# design.net
KiCad netlist of a schematic drawn in Altium Designer
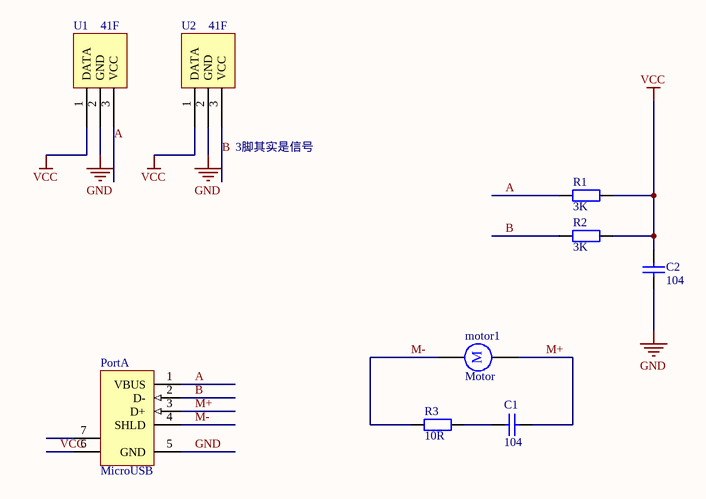
[diagram p0: 电机小板（霍尔编码器）的原理图.SchDoc]

(export (version "E")
  (design (tool "Eeschema 10.0.6"))
  (components
    (comp (ref "C1")
      (value "104")
      (footprint "0805")
      (description "Capacitor")
      (fields (field (name "Comment") "Cap") (field (name "PUBLISHER") "Altium Limited"))
      (libsource (lib "Miscellaneous Devices") (part "Cap"))
    )
    (comp (ref "C2")
      (value "104")
      (footprint "0805")
      (description "Capacitor")
      (fields (field (name "Comment") "Cap") (field (name "PUBLISHER") "Altium Limited"))
      (libsource (lib "Miscellaneous Devices") (part "Cap"))
    )
    (comp (ref "motor1")
      (value "Motor")
      (footprint "RB5-10.5")
      (description "Motor, General Kind")
      (fields (field (name "PUBLISHER") "Altium Limited"))
      (libsource (lib "Miscellaneous Devices") (part "Motor"))
    )
    (comp (ref "PortA")
      (value "MicroUSB")
      (footprint "USB6P")
      (description "USB 2.0, Right Angle, SMT, A Type, Receptacle, 5 Position, Black")
      (fields (field (name "PUBLISHER") "Altium Limited"))
      (libsource (lib "F300") (part "440478-2"))
    )
    (comp (ref "R1")
      (value "3K")
      (footprint "0805")
      (description "Resistor")
      (fields (field (name "Comment") "res2") (field (name "PUBLISHER") "Altium Limited"))
      (libsource (lib "Miscellaneous Devices") (part "Res2"))
    )
    (comp (ref "R2")
      (value "3K")
      (footprint "0805")
      (description "Resistor")
      (fields (field (name "Comment") "res2") (field (name "PUBLISHER") "Altium Limited"))
      (libsource (lib "Miscellaneous Devices") (part "Res2"))
    )
    (comp (ref "R3")
      (value "10R")
      (footprint "0805")
      (description "Resistor")
      (fields (field (name "Comment") "res2") (field (name "PUBLISHER") "Altium Limited"))
      (libsource (lib "Miscellaneous Devices") (part "Res2"))
    )
    (comp (ref "U1") (value "41F") (footprint "HS0038") (libsource (lib "Schlib1") (part "HS0038")))
    (comp (ref "U2") (value "41F") (footprint "HS0038") (libsource (lib "Schlib1") (part "HS0038")))
  )
  (nets
    (net (code "1") (name "/A") (class "Default")
      (node (ref "PortA") (pin "1") (pinfunction "VBUS_1") (pintype "power_in"))
      (node (ref "R1") (pin "1") (pinfunction "1_1") (pintype "passive"))
      (node (ref "U1") (pin "3") (pinfunction "VCC_3") (pintype "passive"))
    )
    (net (code "2") (name "/B") (class "Default")
      (node (ref "PortA") (pin "2") (pinfunction "D-_2") (pintype "input"))
      (node (ref "R2") (pin "1") (pinfunction "1_1") (pintype "passive"))
      (node (ref "U2") (pin "3") (pinfunction "VCC_3") (pintype "passive"))
    )
    (net (code "3") (name "/M+") (class "Default")
      (node (ref "C1") (pin "1") (pinfunction "1_1") (pintype "passive"))
      (node (ref "PortA") (pin "3") (pinfunction "D+_3") (pintype "input"))
      (node (ref "motor1") (pin "2") (pinfunction "2_2") (pintype "passive"))
    )
    (net (code "4") (name "/M-") (class "Default")
      (node (ref "PortA") (pin "4") (pinfunction "SHLD_4") (pintype "passive"))
      (node (ref "R3") (pin "1") (pinfunction "1_1") (pintype "passive"))
      (node (ref "motor1") (pin "1") (pinfunction "1_1") (pintype "passive"))
    )
    (net (code "5") (name "GND") (class "Default")
      (node (ref "C2") (pin "2") (pinfunction "2_2") (pintype "passive"))
      (node (ref "PortA") (pin "5") (pinfunction "GND_5") (pintype "power_in"))
      (node (ref "U1") (pin "2") (pinfunction "GND_2") (pintype "passive"))
      (node (ref "U2") (pin "2") (pinfunction "GND_2") (pintype "passive"))
    )
    (net (code "6") (name "Net-(C1-Pad2)") (class "Default")
      (node (ref "C1") (pin "2") (pinfunction "2_2") (pintype "passive"))
      (node (ref "R3") (pin "2") (pinfunction "2_2") (pintype "passive"))
    )
    (net (code "7") (name "VCC") (class "Default")
      (node (ref "C2") (pin "1") (pinfunction "1_1") (pintype "passive"))
      (node (ref "PortA") (pin "6") (pinfunction "SHLD_6") (pintype "passive"))
      (node (ref "R1") (pin "2") (pinfunction "2_2") (pintype "passive"))
      (node (ref "R2") (pin "2") (pinfunction "2_2") (pintype "passive"))
      (node (ref "U1") (pin "1") (pinfunction "DATA_1") (pintype "passive"))
      (node (ref "U2") (pin "1") (pinfunction "DATA_1") (pintype "passive"))
    )
    (net (code "8") (name "unconnected-(PortA-SHLD-Pad7)") (class "Default")
      (node (ref "PortA") (pin "7") (pinfunction "SHLD_7") (pintype "passive"))
    )
  )
)
